# BuckBoost.net
KiCad netlist of a schematic drawn in Altium Designer
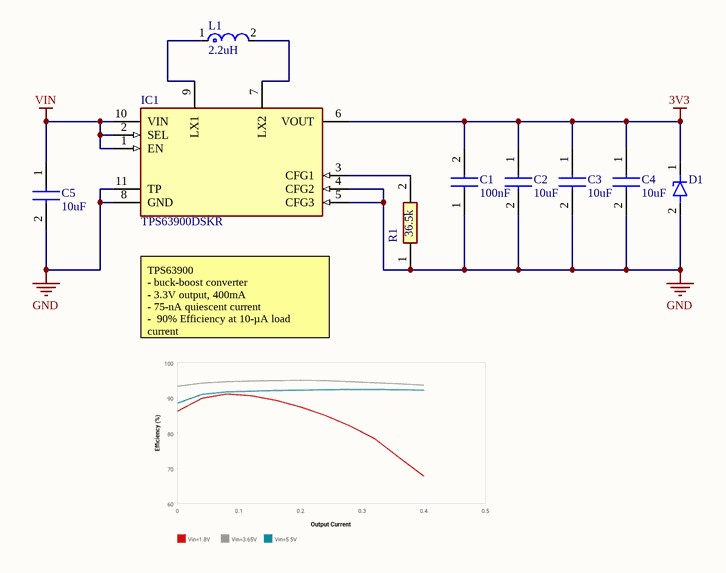
[diagram p0: BuckBoost.SchDoc]

(export (version "E")
  (design (tool "Eeschema 10.0.6"))
  (components
    (comp (ref "C1")
      (value "100nF")
      (footprint "SamacSys:CAPC1005X70N")
      (description "Capacitor")
      (fields
        (field (name "MANUFACTURER_PART_NUMBER") "GRM155R61A104KA01D")
        (field (name "MOUSER PART NUMBER") "81-GRM155R61A104KA01")
      )
      (libsource (lib "*") (part "GRM155R61A104KA01D"))
    )
    (comp (ref "C2")
      (value "10uF")
      (footprint "SamacSys:GRM18x")
      (description "Capacitor")
      (fields
        (field (name "MANUFACTURER_PART_NUMBER") "GRM188R61E106KA73D")
        (field (name "MOUSER PART NUMBER") "81-GRM188R61E106KA3D")
      )
      (libsource (lib "*") (part "GRM188R61E106KA73D"))
    )
    (comp (ref "C3")
      (value "10uF")
      (footprint "SamacSys:GRM18x")
      (description "Capacitor")
      (fields
        (field (name "MANUFACTURER_PART_NUMBER") "GRM188R61E106KA73D")
        (field (name "MOUSER PART NUMBER") "81-GRM188R61E106KA3D")
      )
      (libsource (lib "*") (part "GRM188R61E106KA73D"))
    )
    (comp (ref "C4")
      (value "10uF")
      (footprint "SamacSys:GRM18x")
      (description "Capacitor")
      (fields
        (field (name "MANUFACTURER_PART_NUMBER") "GRM188R61E106KA73D")
        (field (name "MOUSER PART NUMBER") "81-GRM188R61E106KA3D")
      )
      (libsource (lib "*") (part "GRM188R61E106KA73D"))
    )
    (comp (ref "C5")
      (value "10uF")
      (footprint "SamacSys:GRM18x")
      (description "Capacitor")
      (fields
        (field (name "MANUFACTURER_PART_NUMBER") "GRM188R61E106KA73D")
        (field (name "MOUSER PART NUMBER") "81-GRM188R61E106KA3D")
      )
      (libsource (lib "*") (part "GRM188R61E106KA73D"))
    )
    (comp (ref "D1")
      (value "SP3205-01ETG")
      (footprint "SamacSys:SP320501ETG")
      (description "Diode ESD (Uni-directional)")
      (fields (field (name "MOUSER PART NUMBER") "576-SP3205-01ETG"))
      (libsource (lib "SamacSys") (part "SP3205-01ETG"))
    )
    (comp (ref "IC1")
      (value "TPS63900DSKR")
      (footprint "SamacSys:SON50P250X250X80-11N-D")
      (description "Integrated Circuit")
      (fields (field (name "MOUSER PART NUMBER") "595-TPS63900DSKR"))
      (libsource (lib "SamacSys") (part "TPS63900DSKR"))
    )
    (comp (ref "L1")
      (value "2.2uH")
      (footprint "FP-XFL4020-MFG")
      (description "INDUCTOR, 2.2UH, 8A, 20%, 38MHZ, REEL")
      (fields (field (name "TOLERANCE") "20%"))
      (libsource (lib "Altium Content Vault") (part "4cc4b267dca4c8e51f7102f422741d8"))
    )
    (comp (ref "R1")
      (value "36.5k")
      (footprint "SamacSys:RESC1005X35N")
      (description "Resistor")
      (fields
        (field (name "MANUFACTURER_PART_NUMBER") "RP0402BRD0736K5L")
        (field (name "MOUSER PART NUMBER") "603-RT0402FRE07100KL")
      )
      (libsource (lib "SamacSys") (part "RP0402BRD0736K5L"))
    )
  )
  (nets
    (net (code "1") (name "3V3") (class "Default")
      (node (ref "C1") (pin "2") (pinfunction "2_2") (pintype "passive"))
      (node (ref "C2") (pin "1") (pinfunction "1_1") (pintype "passive"))
      (node (ref "C3") (pin "1") (pinfunction "1_1") (pintype "passive"))
      (node (ref "C4") (pin "1") (pinfunction "1_1") (pintype "passive"))
      (node (ref "D1") (pin "1") (pinfunction "K_1") (pintype "passive"))
      (node (ref "IC1") (pin "6") (pinfunction "VOUT_6") (pintype "power_in"))
    )
    (net (code "2") (name "GND") (class "Default")
      (node (ref "C1") (pin "1") (pinfunction "1_1") (pintype "passive"))
      (node (ref "C2") (pin "2") (pinfunction "2_2") (pintype "passive"))
      (node (ref "C3") (pin "2") (pinfunction "2_2") (pintype "passive"))
      (node (ref "C4") (pin "2") (pinfunction "2_2") (pintype "passive"))
      (node (ref "C5") (pin "2") (pinfunction "2_2") (pintype "passive"))
      (node (ref "D1") (pin "2") (pinfunction "A_2") (pintype "passive"))
      (node (ref "IC1") (pin "11") (pinfunction "TP_11") (pintype "power_in"))
      (node (ref "IC1") (pin "4") (pinfunction "CFG2_4") (pintype "input"))
      (node (ref "IC1") (pin "5") (pinfunction "CFG3_5") (pintype "input"))
      (node (ref "IC1") (pin "8") (pinfunction "GND_8") (pintype "power_in"))
      (node (ref "R1") (pin "1") (pinfunction "1_1") (pintype "passive"))
    )
    (net (code "3") (name "Net-(IC1-CFG1)") (class "Default")
      (node (ref "IC1") (pin "3") (pinfunction "CFG1_3") (pintype "input"))
      (node (ref "R1") (pin "2") (pinfunction "2_2") (pintype "passive"))
    )
    (net (code "4") (name "Net-(IC1-LX1)") (class "Default")
      (node (ref "IC1") (pin "9") (pinfunction "LX1_9") (pintype "power_in"))
      (node (ref "L1") (pin "1") (pinfunction "1_1") (pintype "passive"))
    )
    (net (code "5") (name "Net-(IC1-LX2)") (class "Default")
      (node (ref "IC1") (pin "7") (pinfunction "LX2_7") (pintype "power_in"))
      (node (ref "L1") (pin "2") (pinfunction "2_2") (pintype "passive"))
    )
    (net (code "6") (name "VIN") (class "Default")
      (node (ref "C5") (pin "1") (pinfunction "1_1") (pintype "passive"))
      (node (ref "IC1") (pin "1") (pinfunction "EN_1") (pintype "input"))
      (node (ref "IC1") (pin "10") (pinfunction "VIN_10") (pintype "power_in"))
      (node (ref "IC1") (pin "2") (pinfunction "SEL_2") (pintype "input"))
    )
  )
)
